# SensorInterface.net
KiCad netlist of a schematic drawn in Altium Designer
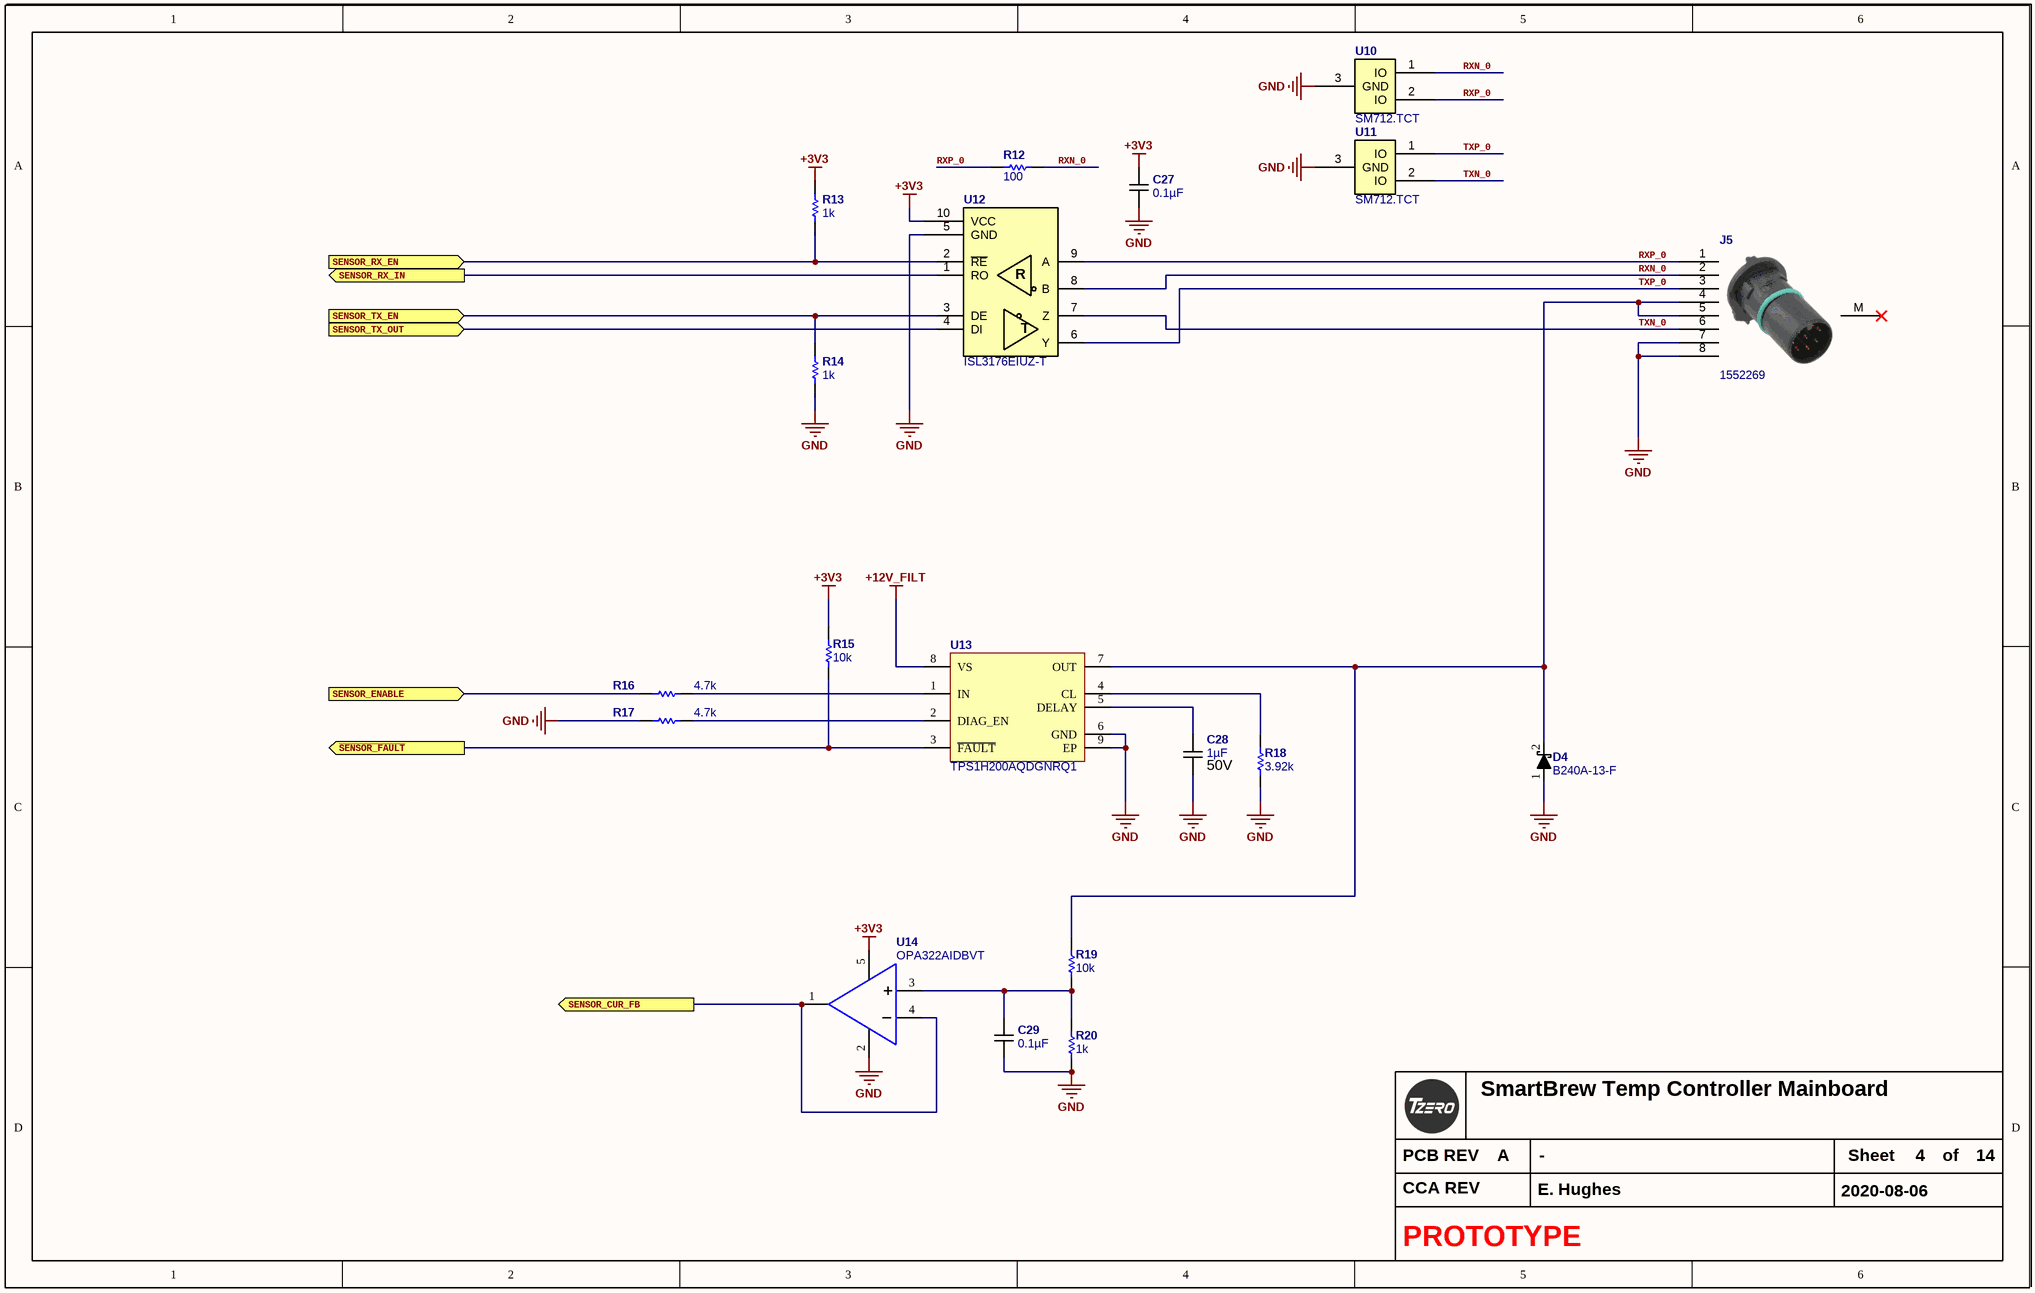
[diagram p0: SensorInterface.SchDoc]

(export (version "E")
  (design (tool "Eeschema 10.0.6"))
  (components
    (comp (ref "C27")
      (value "0.1µF")
      (footprint "C0402_0.55MM_HD")
      (description "CAP CER 0.1UF 25V X7R 0402")
      (fields
        (field (name "MANUFACTURER PART NUMBER") "CGA2B3X7R1E104K050BB")
        (field (name "MANUFACTURER") "TDK Corporation")
      )
      (libsource (lib "Capacitors - TDK- AEC-Q200") (part "C_2P_NP"))
    )
    (comp (ref "C28")
      (value "1µF")
      (footprint "C0805_1.50MM_MD")
      (description "CAP CER 1UF 50V X7R 0805")
      (fields
        (field (name "MANUFACTURER PART NUMBER") "CGA4J3X7R1H105M125AE")
        (field (name "MANUFACTURER") "TDK Corporation")
        (field (name "VOLTAGE - RATED") "50V")
      )
      (libsource (lib "Capacitors - TDK- AEC-Q200") (part "C_2P_NP"))
    )
    (comp (ref "C29")
      (value "0.1µF")
      (footprint "C0402_0.55MM_HD")
      (description "CAP CER 0.1UF 25V X7R 0402")
      (fields
        (field (name "MANUFACTURER PART NUMBER") "CGA2B3X7R1E104K050BB")
        (field (name "MANUFACTURER") "TDK Corporation")
      )
      (libsource (lib "Capacitors - TDK- AEC-Q200") (part "C_2P_NP"))
    )
    (comp (ref "D4")
      (value "B240A-13-F")
      (footprint "D_SMA_P")
      (description "DIODE SCHOTTKY 40V 2A SMA")
      (fields (field (name "MANUFACTURER") "Diodes Inc"))
      (libsource (lib "Diodes") (part "DS_1A_2C"))
    )
    (comp (ref "J5")
      (value "1552269")
      (footprint "1552269")
      (description "Circular Metric Connectors SACC-DSI-FSD -4CON-PG9/0,5 SCO")
      (fields (field (name "MANUFACTURER") "Phoenix Contact"))
      (libsource (lib "eConnector_Phoenix_M12") (part "1552269"))
    )
    (comp (ref "R12")
      (value "100")
      (footprint "R0603_0.55MM_MD")
      (description "RES 100 OHM 1/10W 1% 0603 SMD")
      (fields
        (field (name "MANUFACTURER PART NUMBER") "ERJ-3EKF1000V")
        (field (name "MANUFACTURER") "Panasonic Electronic Components")
      )
      (libsource (lib "Resistors - Panasonic - AEC-Q200") (part "R_2P"))
    )
    (comp (ref "R13")
      (value "1k")
      (footprint "R0603_0.55MM_MD")
      (description "RES 1K OHM 1/10W 1% 0603 SMD")
      (fields
        (field (name "MANUFACTURER PART NUMBER") "ERJ-3EKF1001V")
        (field (name "MANUFACTURER") "Panasonic Electronic Components")
      )
      (libsource (lib "Resistors - Panasonic - AEC-Q200") (part "R_2P"))
    )
    (comp (ref "R14")
      (value "1k")
      (footprint "R0603_0.55MM_MD")
      (description "RES 1K OHM 1/10W 1% 0603 SMD")
      (fields
        (field (name "MANUFACTURER PART NUMBER") "ERJ-3EKF1001V")
        (field (name "MANUFACTURER") "Panasonic Electronic Components")
      )
      (libsource (lib "Resistors - Panasonic - AEC-Q200") (part "R_2P"))
    )
    (comp (ref "R15")
      (value "10k")
      (footprint "R0603_0.55MM_MD")
      (description "RES 10K OHM 1/10W 1% 0603 SMD")
      (fields
        (field (name "MANUFACTURER PART NUMBER") "ERJ-3EKF1002V")
        (field (name "MANUFACTURER") "Panasonic Electronic Components")
      )
      (libsource (lib "Resistors - Panasonic - AEC-Q200") (part "R_2P"))
    )
    (comp (ref "R16")
      (value "4.7k")
      (footprint "R0603_0.55MM_MD")
      (description "RES 4.7K OHM 1/10W 1% 0603 SMD")
      (fields
        (field (name "MANUFACTURER PART NUMBER") "ERJ-3EKF4701V")
        (field (name "MANUFACTURER") "Panasonic Electronic Components")
      )
      (libsource (lib "Resistors - Panasonic - AEC-Q200") (part "R_2P"))
    )
    (comp (ref "R17")
      (value "4.7k")
      (footprint "R0603_0.55MM_MD")
      (description "RES 4.7K OHM 1/10W 1% 0603 SMD")
      (fields
        (field (name "MANUFACTURER PART NUMBER") "ERJ-3EKF4701V")
        (field (name "MANUFACTURER") "Panasonic Electronic Components")
      )
      (libsource (lib "Resistors - Panasonic - AEC-Q200") (part "R_2P"))
    )
    (comp (ref "R18")
      (value "3.92k")
      (footprint "R0603_0.55MM_MD")
      (description "RES 3.92K OHM 1/10W 1% 0603 SMD")
      (fields
        (field (name "MANUFACTURER PART NUMBER") "ERJ-3EKF3921V")
        (field (name "MANUFACTURER") "Panasonic Electronic Components")
      )
      (libsource (lib "Resistors - Panasonic - AEC-Q200") (part "R_2P"))
    )
    (comp (ref "R19")
      (value "10k")
      (footprint "R0603_0.55MM_MD")
      (description "RES 10K OHM 1/10W 1% 0603 SMD")
      (fields
        (field (name "MANUFACTURER PART NUMBER") "ERJ-3EKF1002V")
        (field (name "MANUFACTURER") "Panasonic Electronic Components")
      )
      (libsource (lib "Resistors - Panasonic - AEC-Q200") (part "R_2P"))
    )
    (comp (ref "R20")
      (value "1k")
      (footprint "R0603_0.55MM_MD")
      (description "RES 1K OHM 1/10W 1% 0603 SMD")
      (fields
        (field (name "MANUFACTURER PART NUMBER") "ERJ-3EKF1001V")
        (field (name "MANUFACTURER") "Panasonic Electronic Components")
      )
      (libsource (lib "Resistors - Panasonic - AEC-Q200") (part "R_2P"))
    )
    (comp (ref "U10")
      (value "SM712.TCT")
      (footprint "SOT-23")
      (description "TVS DIODE 12VWM/7VWM SOT23")
      (fields (field (name "MANUFACTURER") "Semtech"))
      (libsource (lib "eDiode") (part "SM712.TCT"))
    )
    (comp (ref "U11")
      (value "SM712.TCT")
      (footprint "SOT-23")
      (description "TVS DIODE 12VWM/7VWM SOT23")
      (fields (field (name "MANUFACTURER") "Semtech"))
      (libsource (lib "eDiode") (part "SM712.TCT"))
    )
    (comp (ref "U12")
      (value "ISL3176EIUZ-T")
      (footprint "10 MSOP")
      (description "IC TXRX RS422/485 20MBPS 10MSOP")
      (fields (field (name "MANUFACTURER") "Intersil"))
      (libsource (lib "eIC") (part "ISL3176EIUZ-T"))
    )
    (comp (ref "U13")
      (value "TPS1H200AQDGNRQ1")
      (footprint "TI_DGN_MD")
      (description "SINGLE CHANNEL HIGH SIDE POWER S")
      (fields (field (name "MANUFACTURER") "Texas Instruments"))
      (libsource (lib "Transistors-N") (part "TPS1H200AQDGNRQ1"))
    )
    (comp (ref "U14")
      (value "OPA322AIDBVT")
      (footprint "SOT23-5")
      (description "IC OPAMP GP 20MHZ RRO SOT23-5")
      (fields (field (name "MANUFACTURER") "Texas Instruments"))
      (libsource (lib "eOPAMP") (part "OPA322AIDBVT"))
    )
  )
  (nets
    (net (code "1") (name "+3V3") (class "Default")
      (node (ref "C27") (pin "2") (pinfunction "1_2") (pintype "passive"))
      (node (ref "R13") (pin "1") (pinfunction "1_1") (pintype "passive"))
      (node (ref "R15") (pin "2") (pinfunction "2_2") (pintype "passive"))
      (node (ref "U12") (pin "10") (pinfunction "VCC_10") (pintype "passive"))
      (node (ref "U14") (pin "5") (pinfunction "VCC_5") (pintype "passive"))
    )
    (net (code "2") (name "+12V_FILT") (class "Default")
      (node (ref "U13") (pin "8") (pinfunction "VS_8") (pintype "passive"))
    )
    (net (code "3") (name "/RXN_0") (class "Default")
      (node (ref "J5") (pin "2") (pinfunction "2_2") (pintype "passive"))
      (node (ref "R12") (pin "2") (pinfunction "2_2") (pintype "passive"))
      (node (ref "U10") (pin "1") (pinfunction "IO_1") (pintype "passive"))
      (node (ref "U12") (pin "8") (pinfunction "B_8") (pintype "passive"))
    )
    (net (code "4") (name "/RXP_0") (class "Default")
      (node (ref "J5") (pin "1") (pinfunction "1_1") (pintype "passive"))
      (node (ref "R12") (pin "1") (pinfunction "1_1") (pintype "passive"))
      (node (ref "U10") (pin "2") (pinfunction "IO_2") (pintype "passive"))
      (node (ref "U12") (pin "9") (pinfunction "A_9") (pintype "passive"))
    )
    (net (code "5") (name "/SENSOR_CUR_FB") (class "Default")
      (node (ref "U14") (pin "1") (pinfunction "OUT_1") (pintype "passive"))
      (node (ref "U14") (pin "4") (pinfunction "-_4") (pintype "passive"))
    )
    (net (code "6") (name "/SENSOR_ENABLE") (class "Default")
      (node (ref "R16") (pin "1") (pinfunction "1_1") (pintype "passive"))
    )
    (net (code "7") (name "/SENSOR_FAULT") (class "Default")
      (node (ref "R15") (pin "1") (pinfunction "1_1") (pintype "passive"))
      (node (ref "U13") (pin "3") (pinfunction "FAULT_3") (pintype "passive"))
    )
    (net (code "8") (name "/SENSOR_RX_EN") (class "Default")
      (node (ref "R13") (pin "2") (pinfunction "2_2") (pintype "passive"))
      (node (ref "U12") (pin "2") (pinfunction "~{RE}_2") (pintype "passive"))
    )
    (net (code "9") (name "/SENSOR_RX_IN") (class "Default")
      (node (ref "U12") (pin "1") (pinfunction "RO_1") (pintype "passive"))
    )
    (net (code "10") (name "/SENSOR_TX_EN") (class "Default")
      (node (ref "R14") (pin "1") (pinfunction "1_1") (pintype "passive"))
      (node (ref "U12") (pin "3") (pinfunction "DE_3") (pintype "passive"))
    )
    (net (code "11") (name "/SENSOR_TX_OUT") (class "Default")
      (node (ref "U12") (pin "4") (pinfunction "DI_4") (pintype "passive"))
    )
    (net (code "12") (name "/TXN_0") (class "Default")
      (node (ref "J5") (pin "6") (pinfunction "6_6") (pintype "passive"))
      (node (ref "U11") (pin "2") (pinfunction "IO_2") (pintype "passive"))
      (node (ref "U12") (pin "7") (pinfunction "Z_7") (pintype "passive"))
    )
    (net (code "13") (name "/TXP_0") (class "Default")
      (node (ref "J5") (pin "3") (pinfunction "3_3") (pintype "passive"))
      (node (ref "U11") (pin "1") (pinfunction "IO_1") (pintype "passive"))
      (node (ref "U12") (pin "6") (pinfunction "Y_6") (pintype "passive"))
    )
    (net (code "14") (name "GND") (class "Default")
      (node (ref "C27") (pin "1") (pinfunction "1_1") (pintype "passive"))
      (node (ref "C28") (pin "1") (pinfunction "1_1") (pintype "passive"))
      (node (ref "C29") (pin "1") (pinfunction "1_1") (pintype "passive"))
      (node (ref "D4") (pin "1") (pinfunction "A_1") (pintype "passive"))
      (node (ref "J5") (pin "7") (pinfunction "7_7") (pintype "passive"))
      (node (ref "J5") (pin "8") (pinfunction "8_8") (pintype "passive"))
      (node (ref "R14") (pin "2") (pinfunction "2_2") (pintype "passive"))
      (node (ref "R17") (pin "1") (pinfunction "1_1") (pintype "passive"))
      (node (ref "R18") (pin "1") (pinfunction "1_1") (pintype "passive"))
      (node (ref "R20") (pin "2") (pinfunction "2_2") (pintype "passive"))
      (node (ref "U10") (pin "3") (pinfunction "GND_3") (pintype "passive"))
      (node (ref "U11") (pin "3") (pinfunction "GND_3") (pintype "passive"))
      (node (ref "U12") (pin "5") (pinfunction "GND_5") (pintype "passive"))
      (node (ref "U13") (pin "6") (pinfunction "GND_6") (pintype "passive"))
      (node (ref "U13") (pin "9") (pinfunction "EP_9") (pintype "passive"))
      (node (ref "U14") (pin "2") (pinfunction "GND_2") (pintype "passive"))
    )
    (net (code "15") (name "Net-(D4-K)") (class "Default")
      (node (ref "D4") (pin "2") (pinfunction "K_2") (pintype "passive"))
      (node (ref "J5") (pin "4") (pinfunction "4_4") (pintype "passive"))
      (node (ref "J5") (pin "5") (pinfunction "5_5") (pintype "passive"))
      (node (ref "R19") (pin "2") (pinfunction "2_2") (pintype "passive"))
      (node (ref "U13") (pin "7") (pinfunction "OUT_7") (pintype "passive"))
    )
    (net (code "16") (name "Net-(U13-CL)") (class "Default")
      (node (ref "R18") (pin "2") (pinfunction "2_2") (pintype "passive"))
      (node (ref "U13") (pin "4") (pinfunction "CL_4") (pintype "passive"))
    )
    (net (code "17") (name "Net-(U13-DELAY)") (class "Default")
      (node (ref "C28") (pin "2") (pinfunction "1_2") (pintype "passive"))
      (node (ref "U13") (pin "5") (pinfunction "DELAY_5") (pintype "passive"))
    )
    (net (code "18") (name "Net-(U13-DIAG_EN)") (class "Default")
      (node (ref "R17") (pin "2") (pinfunction "2_2") (pintype "passive"))
      (node (ref "U13") (pin "2") (pinfunction "DIAG_EN_2") (pintype "passive"))
    )
    (net (code "19") (name "Net-(U13-IN)") (class "Default")
      (node (ref "R16") (pin "2") (pinfunction "2_2") (pintype "passive"))
      (node (ref "U13") (pin "1") (pinfunction "IN_1") (pintype "passive"))
    )
    (net (code "20") (name "Net-(U14-+)") (class "Default")
      (node (ref "C29") (pin "2") (pinfunction "1_2") (pintype "passive"))
      (node (ref "R19") (pin "1") (pinfunction "1_1") (pintype "passive"))
      (node (ref "R20") (pin "1") (pinfunction "1_1") (pintype "passive"))
      (node (ref "U14") (pin "3") (pinfunction "+_3") (pintype "passive"))
    )
    (net (code "21") (name "unconnected-(J5-PadM)") (class "Default")
      (node (ref "J5") (pin "M") (pinfunction "M_M") (pintype "passive+no_connect"))
    )
  )
)
